# CPU_-_POWER_RAILS.net
KiCad netlist of a schematic drawn in Altium Designer
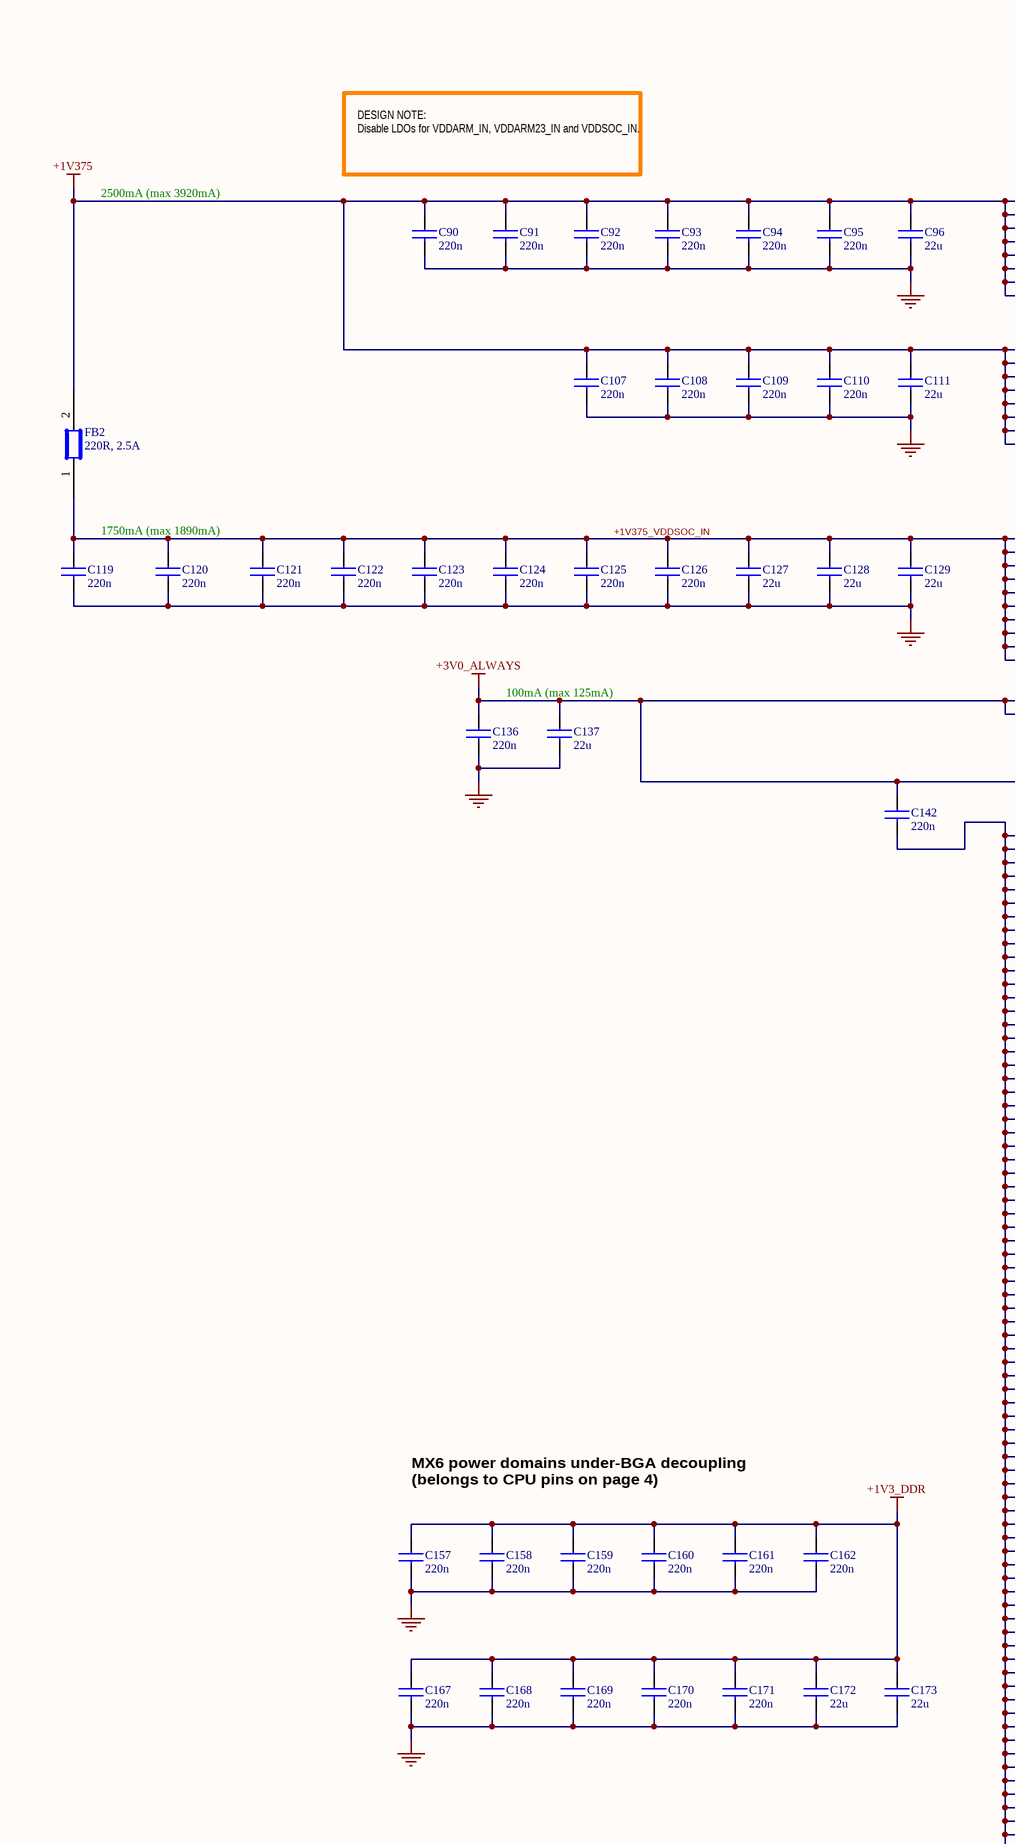
[diagram p0: CPU - POWER RAILS.SchDoc, left]
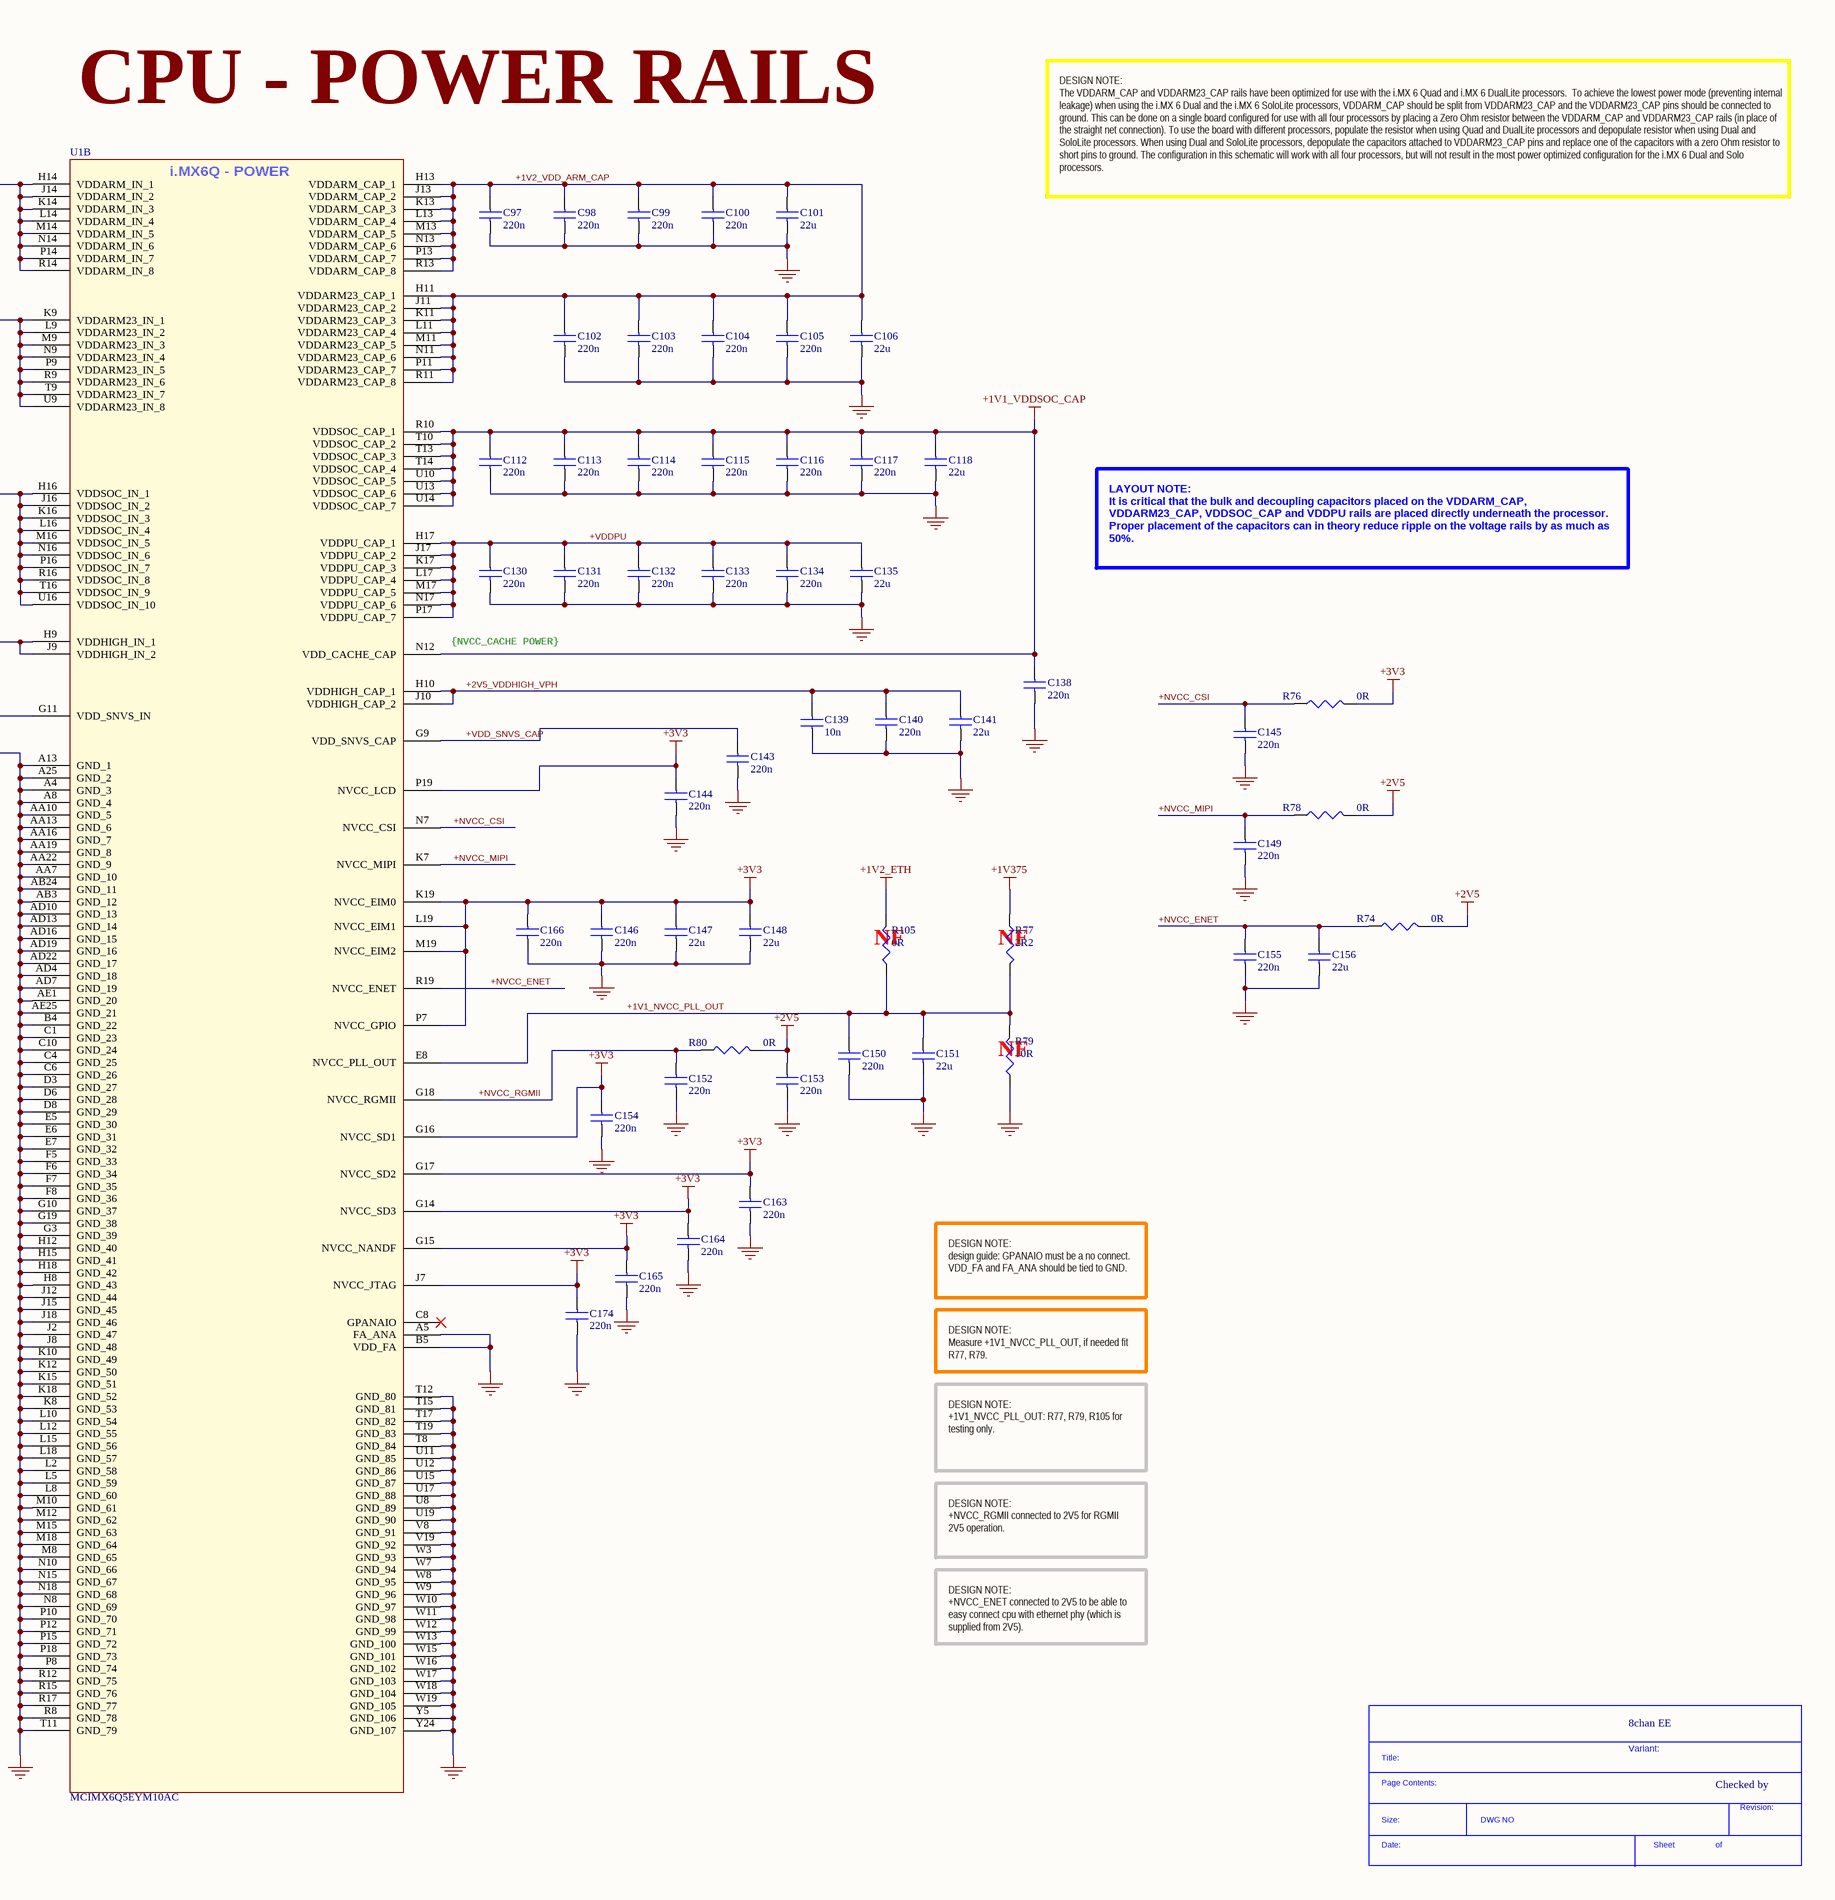
[diagram p1: CPU - POWER RAILS.SchDoc, right]

(export (version "E")
  (design (tool "Eeschema 10.0.6"))
  (components
    (comp (ref "*") (value "SDTitleBlock") (libsource (lib "*") (part "SDTitleBlock")))
    (comp (ref "C90")
      (value "220n")
      (footprint "C0402")
      (description "CAP CER .22UF 25V X5R 20% 0402")
      (fields
        (field (name "MANUFACTURER") "TDK Corporation")
        (field (name "MANUFACTURER PART NUMBER") "C1005X5R1E224M")
      )
      (libsource (lib "Integrated_Library_RF_FEB_2012") (part "C1005X5R1E224M"))
    )
    (comp (ref "C91")
      (value "220n")
      (footprint "C0402")
      (description "CAP CER .22UF 25V X5R 20% 0402")
      (fields
        (field (name "MANUFACTURER") "TDK Corporation")
        (field (name "MANUFACTURER PART NUMBER") "C1005X5R1E224M")
      )
      (libsource (lib "Integrated_Library_RF_FEB_2012") (part "C1005X5R1E224M"))
    )
    (comp (ref "C92")
      (value "220n")
      (footprint "C0402")
      (description "CAP CER .22UF 25V X5R 20% 0402")
      (fields
        (field (name "MANUFACTURER") "TDK Corporation")
        (field (name "MANUFACTURER PART NUMBER") "C1005X5R1E224M")
      )
      (libsource (lib "Integrated_Library_RF_FEB_2012") (part "C1005X5R1E224M"))
    )
    (comp (ref "C93")
      (value "220n")
      (footprint "C0402")
      (description "CAP CER .22UF 25V X5R 20% 0402")
      (fields
        (field (name "MANUFACTURER") "TDK Corporation")
        (field (name "MANUFACTURER PART NUMBER") "C1005X5R1E224M")
      )
      (libsource (lib "Integrated_Library_RF_FEB_2012") (part "C1005X5R1E224M"))
    )
    (comp (ref "C94")
      (value "220n")
      (footprint "C0402")
      (description "CAP CER .22UF 25V X5R 20% 0402")
      (fields
        (field (name "MANUFACTURER") "TDK Corporation")
        (field (name "MANUFACTURER PART NUMBER") "C1005X5R1E224M")
      )
      (libsource (lib "Integrated_Library_RF_FEB_2012") (part "C1005X5R1E224M"))
    )
    (comp (ref "C95")
      (value "220n")
      (footprint "C0402")
      (description "CAP CER .22UF 25V X5R 20% 0402")
      (fields
        (field (name "MANUFACTURER") "TDK Corporation")
        (field (name "MANUFACTURER PART NUMBER") "C1005X5R1E224M")
      )
      (libsource (lib "Integrated_Library_RF_FEB_2012") (part "C1005X5R1E224M"))
    )
    (comp (ref "C96")
      (value "22u")
      (footprint "C0603")
      (description "CAP CER 22UF 4V 20% X5R 0603")
      (fields
        (field (name "MANUFACTURER") "Murata Electronics North America")
        (field (name "MANUFACTURER PART NUMBER") "GRM188R60G226MEA0L")
        (field (name ".CHECKED PCB") "RF, used by MM")
        (field (name ".CHECKED SCH") "MM, checked by RF")
        (field (name ".CREATOR") "MM")
      )
      (libsource (lib "Schlib_RF") (part "GRM188R60G226MEA0L"))
    )
    (comp (ref "C97")
      (value "220n")
      (footprint "C0402")
      (description "CAP CER .22UF 25V X5R 20% 0402")
      (fields
        (field (name "MANUFACTURER") "TDK Corporation")
        (field (name "MANUFACTURER PART NUMBER") "C1005X5R1E224M")
      )
      (libsource (lib "Integrated_Library_RF_FEB_2012") (part "C1005X5R1E224M"))
    )
    (comp (ref "C98")
      (value "220n")
      (footprint "C0402")
      (description "CAP CER .22UF 25V X5R 20% 0402")
      (fields
        (field (name "MANUFACTURER") "TDK Corporation")
        (field (name "MANUFACTURER PART NUMBER") "C1005X5R1E224M")
      )
      (libsource (lib "Integrated_Library_RF_FEB_2012") (part "C1005X5R1E224M"))
    )
    (comp (ref "C99")
      (value "220n")
      (footprint "C0402")
      (description "CAP CER .22UF 25V X5R 20% 0402")
      (fields
        (field (name "MANUFACTURER") "TDK Corporation")
        (field (name "MANUFACTURER PART NUMBER") "C1005X5R1E224M")
      )
      (libsource (lib "Integrated_Library_RF_FEB_2012") (part "C1005X5R1E224M"))
    )
    (comp (ref "C100")
      (value "220n")
      (footprint "C0402")
      (description "CAP CER .22UF 25V X5R 20% 0402")
      (fields
        (field (name "MANUFACTURER") "TDK Corporation")
        (field (name "MANUFACTURER PART NUMBER") "C1005X5R1E224M")
      )
      (libsource (lib "Integrated_Library_RF_FEB_2012") (part "C1005X5R1E224M"))
    )
    (comp (ref "C101")
      (value "22u")
      (footprint "C0603")
      (description "CAP CER 22UF 4V 20% X5R 0603")
      (fields
        (field (name "MANUFACTURER") "Murata Electronics North America")
        (field (name "MANUFACTURER PART NUMBER") "GRM188R60G226MEA0L")
        (field (name ".CHECKED PCB") "RF, used by MM")
        (field (name ".CHECKED SCH") "MM, checked by RF")
        (field (name ".CREATOR") "MM")
      )
      (libsource (lib "Schlib_RF") (part "GRM188R60G226MEA0L"))
    )
    (comp (ref "C102")
      (value "220n")
      (footprint "C0402")
      (description "CAP CER .22UF 25V X5R 20% 0402")
      (fields
        (field (name "MANUFACTURER") "TDK Corporation")
        (field (name "MANUFACTURER PART NUMBER") "C1005X5R1E224M")
      )
      (libsource (lib "Integrated_Library_RF_FEB_2012") (part "C1005X5R1E224M"))
    )
    (comp (ref "C103")
      (value "220n")
      (footprint "C0402")
      (description "CAP CER .22UF 25V X5R 20% 0402")
      (fields
        (field (name "MANUFACTURER") "TDK Corporation")
        (field (name "MANUFACTURER PART NUMBER") "C1005X5R1E224M")
      )
      (libsource (lib "Integrated_Library_RF_FEB_2012") (part "C1005X5R1E224M"))
    )
    (comp (ref "C104")
      (value "220n")
      (footprint "C0402")
      (description "CAP CER .22UF 25V X5R 20% 0402")
      (fields
        (field (name "MANUFACTURER") "TDK Corporation")
        (field (name "MANUFACTURER PART NUMBER") "C1005X5R1E224M")
      )
      (libsource (lib "Integrated_Library_RF_FEB_2012") (part "C1005X5R1E224M"))
    )
    (comp (ref "C105")
      (value "220n")
      (footprint "C0402")
      (description "CAP CER .22UF 25V X5R 20% 0402")
      (fields
        (field (name "MANUFACTURER") "TDK Corporation")
        (field (name "MANUFACTURER PART NUMBER") "C1005X5R1E224M")
      )
      (libsource (lib "Integrated_Library_RF_FEB_2012") (part "C1005X5R1E224M"))
    )
    (comp (ref "C106")
      (value "22u")
      (footprint "C0603")
      (description "CAP CER 22UF 4V 20% X5R 0603")
      (fields
        (field (name "MANUFACTURER") "Murata Electronics North America")
        (field (name "MANUFACTURER PART NUMBER") "GRM188R60G226MEA0L")
        (field (name ".CHECKED PCB") "RF, used by MM")
        (field (name ".CHECKED SCH") "MM, checked by RF")
        (field (name ".CREATOR") "MM")
      )
      (libsource (lib "Schlib_RF") (part "GRM188R60G226MEA0L"))
    )
    (comp (ref "C107")
      (value "220n")
      (footprint "C0402")
      (description "CAP CER .22UF 25V X5R 20% 0402")
      (fields
        (field (name "MANUFACTURER") "TDK Corporation")
        (field (name "MANUFACTURER PART NUMBER") "C1005X5R1E224M")
      )
      (libsource (lib "Integrated_Library_RF_FEB_2012") (part "C1005X5R1E224M"))
    )
    (comp (ref "C108")
      (value "220n")
      (footprint "C0402")
      (description "CAP CER .22UF 25V X5R 20% 0402")
      (fields
        (field (name "MANUFACTURER") "TDK Corporation")
        (field (name "MANUFACTURER PART NUMBER") "C1005X5R1E224M")
      )
      (libsource (lib "Integrated_Library_RF_FEB_2012") (part "C1005X5R1E224M"))
    )
    (comp (ref "C109")
      (value "220n")
      (footprint "C0402")
      (description "CAP CER .22UF 25V X5R 20% 0402")
      (fields
        (field (name "MANUFACTURER") "TDK Corporation")
        (field (name "MANUFACTURER PART NUMBER") "C1005X5R1E224M")
      )
      (libsource (lib "Integrated_Library_RF_FEB_2012") (part "C1005X5R1E224M"))
    )
    (comp (ref "C110")
      (value "220n")
      (footprint "C0402")
      (description "CAP CER .22UF 25V X5R 20% 0402")
      (fields
        (field (name "MANUFACTURER") "TDK Corporation")
        (field (name "MANUFACTURER PART NUMBER") "C1005X5R1E224M")
      )
      (libsource (lib "Integrated_Library_RF_FEB_2012") (part "C1005X5R1E224M"))
    )
    (comp (ref "C111")
      (value "22u")
      (footprint "C0603")
      (description "CAP CER 22UF 4V 20% X5R 0603")
      (fields
        (field (name "MANUFACTURER") "Murata Electronics North America")
        (field (name "MANUFACTURER PART NUMBER") "GRM188R60G226MEA0L")
        (field (name ".CHECKED PCB") "RF, used by MM")
        (field (name ".CHECKED SCH") "MM, checked by RF")
        (field (name ".CREATOR") "MM")
      )
      (libsource (lib "Schlib_RF") (part "GRM188R60G226MEA0L"))
    )
    (comp (ref "C112")
      (value "220n")
      (footprint "C0402")
      (description "CAP CER .22UF 25V X5R 20% 0402")
      (fields
        (field (name "MANUFACTURER") "TDK Corporation")
        (field (name "MANUFACTURER PART NUMBER") "C1005X5R1E224M")
      )
      (libsource (lib "Integrated_Library_RF_FEB_2012") (part "C1005X5R1E224M"))
    )
    (comp (ref "C113")
      (value "220n")
      (footprint "C0402")
      (description "CAP CER .22UF 25V X5R 20% 0402")
      (fields
        (field (name "MANUFACTURER") "TDK Corporation")
        (field (name "MANUFACTURER PART NUMBER") "C1005X5R1E224M")
      )
      (libsource (lib "Integrated_Library_RF_FEB_2012") (part "C1005X5R1E224M"))
    )
    (comp (ref "C114")
      (value "220n")
      (footprint "C0402")
      (description "CAP CER .22UF 25V X5R 20% 0402")
      (fields
        (field (name "MANUFACTURER") "TDK Corporation")
        (field (name "MANUFACTURER PART NUMBER") "C1005X5R1E224M")
      )
      (libsource (lib "Integrated_Library_RF_FEB_2012") (part "C1005X5R1E224M"))
    )
    (comp (ref "C115")
      (value "220n")
      (footprint "C0402")
      (description "CAP CER .22UF 25V X5R 20% 0402")
      (fields
        (field (name "MANUFACTURER") "TDK Corporation")
        (field (name "MANUFACTURER PART NUMBER") "C1005X5R1E224M")
      )
      (libsource (lib "Integrated_Library_RF_FEB_2012") (part "C1005X5R1E224M"))
    )
    (comp (ref "C116")
      (value "220n")
      (footprint "C0402")
      (description "CAP CER .22UF 25V X5R 20% 0402")
      (fields
        (field (name "MANUFACTURER") "TDK Corporation")
        (field (name "MANUFACTURER PART NUMBER") "C1005X5R1E224M")
      )
      (libsource (lib "Integrated_Library_RF_FEB_2012") (part "C1005X5R1E224M"))
    )
    (comp (ref "C117")
      (value "220n")
      (footprint "C0402")
      (description "CAP CER .22UF 25V X5R 20% 0402")
      (fields
        (field (name "MANUFACTURER") "TDK Corporation")
        (field (name "MANUFACTURER PART NUMBER") "C1005X5R1E224M")
      )
      (libsource (lib "Integrated_Library_RF_FEB_2012") (part "C1005X5R1E224M"))
    )
    (comp (ref "C118")
      (value "22u")
      (footprint "C0603")
      (description "CAP CER 22UF 4V 20% X5R 0603")
      (fields
        (field (name "MANUFACTURER") "Murata Electronics North America")
        (field (name "MANUFACTURER PART NUMBER") "GRM188R60G226MEA0L")
        (field (name ".CHECKED PCB") "RF, used by MM")
        (field (name ".CHECKED SCH") "MM, checked by RF")
        (field (name ".CREATOR") "MM")
      )
      (libsource (lib "Schlib_RF") (part "GRM188R60G226MEA0L"))
    )
    (comp (ref "C119")
      (value "220n")
      (footprint "C0402")
      (description "CAP CER .22UF 25V X5R 20% 0402")
      (fields
        (field (name "MANUFACTURER") "TDK Corporation")
        (field (name "MANUFACTURER PART NUMBER") "C1005X5R1E224M")
      )
      (libsource (lib "Integrated_Library_RF_FEB_2012") (part "C1005X5R1E224M"))
    )
    (comp (ref "C120")
      (value "220n")
      (footprint "C0402")
      (description "CAP CER .22UF 25V X5R 20% 0402")
      (fields
        (field (name "MANUFACTURER") "TDK Corporation")
        (field (name "MANUFACTURER PART NUMBER") "C1005X5R1E224M")
      )
      (libsource (lib "Integrated_Library_RF_FEB_2012") (part "C1005X5R1E224M"))
    )
    (comp (ref "C121")
      (value "220n")
      (footprint "C0402")
      (description "CAP CER .22UF 25V X5R 20% 0402")
      (fields
        (field (name "MANUFACTURER") "TDK Corporation")
        (field (name "MANUFACTURER PART NUMBER") "C1005X5R1E224M")
      )
      (libsource (lib "Integrated_Library_RF_FEB_2012") (part "C1005X5R1E224M"))
    )
    (comp (ref "C122")
      (value "220n")
      (footprint "C0402")
      (description "CAP CER .22UF 25V X5R 20% 0402")
      (fields
        (field (name "MANUFACTURER") "TDK Corporation")
        (field (name "MANUFACTURER PART NUMBER") "C1005X5R1E224M")
      )
      (libsource (lib "Integrated_Library_RF_FEB_2012") (part "C1005X5R1E224M"))
    )
    (comp (ref "C123")
      (value "220n")
      (footprint "C0402")
      (description "CAP CER .22UF 25V X5R 20% 0402")
      (fields
        (field (name "MANUFACTURER") "TDK Corporation")
        (field (name "MANUFACTURER PART NUMBER") "C1005X5R1E224M")
      )
      (libsource (lib "Integrated_Library_RF_FEB_2012") (part "C1005X5R1E224M"))
    )
    (comp (ref "C124")
      (value "220n")
      (footprint "C0402")
      (description "CAP CER .22UF 25V X5R 20% 0402")
      (fields
        (field (name "MANUFACTURER") "TDK Corporation")
        (field (name "MANUFACTURER PART NUMBER") "C1005X5R1E224M")
      )
      (libsource (lib "Integrated_Library_RF_FEB_2012") (part "C1005X5R1E224M"))
    )
    (comp (ref "C125")
      (value "220n")
      (footprint "C0402")
      (description "CAP CER .22UF 25V X5R 20% 0402")
      (fields
        (field (name "MANUFACTURER") "TDK Corporation")
        (field (name "MANUFACTURER PART NUMBER") "C1005X5R1E224M")
      )
      (libsource (lib "Integrated_Library_RF_FEB_2012") (part "C1005X5R1E224M"))
    )
    (comp (ref "C126")
      (value "220n")
      (footprint "C0402")
      (description "CAP CER .22UF 25V X5R 20% 0402")
      (fields
        (field (name "MANUFACTURER") "TDK Corporation")
        (field (name "MANUFACTURER PART NUMBER") "C1005X5R1E224M")
      )
      (libsource (lib "Integrated_Library_RF_FEB_2012") (part "C1005X5R1E224M"))
    )
    (comp (ref "C127")
      (value "22u")
      (footprint "C0603")
      (description "CAP CER 22UF 4V 20% X5R 0603")
      (fields
        (field (name "MANUFACTURER") "Murata Electronics North America")
        (field (name "MANUFACTURER PART NUMBER") "GRM188R60G226MEA0L")
        (field (name ".CHECKED PCB") "RF, used by MM")
        (field (name ".CHECKED SCH") "MM, checked by RF")
        (field (name ".CREATOR") "MM")
      )
      (libsource (lib "Schlib_RF") (part "GRM188R60G226MEA0L"))
    )
    (comp (ref "C128")
      (value "22u")
      (footprint "C0603")
      (description "CAP CER 22UF 4V 20% X5R 0603")
      (fields
        (field (name "MANUFACTURER") "Murata Electronics North America")
        (field (name "MANUFACTURER PART NUMBER") "GRM188R60G226MEA0L")
        (field (name ".CHECKED PCB") "RF, used by MM")
        (field (name ".CHECKED SCH") "MM, checked by RF")
        (field (name ".CREATOR") "MM")
      )
      (libsource (lib "Schlib_RF") (part "GRM188R60G226MEA0L"))
    )
    (comp (ref "C129")
      (value "22u")
      (footprint "C0603")
      (description "CAP CER 22UF 4V 20% X5R 0603")
      (fields
        (field (name "MANUFACTURER") "Murata Electronics North America")
        (field (name "MANUFACTURER PART NUMBER") "GRM188R60G226MEA0L")
        (field (name ".CHECKED PCB") "RF, used by MM")
        (field (name ".CHECKED SCH") "MM, checked by RF")
        (field (name ".CREATOR") "MM")
      )
      (libsource (lib "Schlib_RF") (part "GRM188R60G226MEA0L"))
    )
    (comp (ref "C130")
      (value "220n")
      (footprint "C0402")
      (description "CAP CER .22UF 25V X5R 20% 0402")
      (fields
        (field (name "MANUFACTURER") "TDK Corporation")
        (field (name "MANUFACTURER PART NUMBER") "C1005X5R1E224M")
      )
      (libsource (lib "Integrated_Library_RF_FEB_2012") (part "C1005X5R1E224M"))
    )
    (comp (ref "C131")
      (value "220n")
      (footprint "C0402")
      (description "CAP CER .22UF 25V X5R 20% 0402")
      (fields
        (field (name "MANUFACTURER") "TDK Corporation")
        (field (name "MANUFACTURER PART NUMBER") "C1005X5R1E224M")
      )
      (libsource (lib "Integrated_Library_RF_FEB_2012") (part "C1005X5R1E224M"))
    )
    (comp (ref "C132")
      (value "220n")
      (footprint "C0402")
      (description "CAP CER .22UF 25V X5R 20% 0402")
      (fields
        (field (name "MANUFACTURER") "TDK Corporation")
        (field (name "MANUFACTURER PART NUMBER") "C1005X5R1E224M")
      )
      (libsource (lib "Integrated_Library_RF_FEB_2012") (part "C1005X5R1E224M"))
    )
    (comp (ref "C133")
      (value "220n")
      (footprint "C0402")
      (description "CAP CER .22UF 25V X5R 20% 0402")
      (fields
        (field (name "MANUFACTURER") "TDK Corporation")
        (field (name "MANUFACTURER PART NUMBER") "C1005X5R1E224M")
      )
      (libsource (lib "Integrated_Library_RF_FEB_2012") (part "C1005X5R1E224M"))
    )
    (comp (ref "C134")
      (value "220n")
      (footprint "C0402")
      (description "CAP CER .22UF 25V X5R 20% 0402")
      (fields
        (field (name "MANUFACTURER") "TDK Corporation")
        (field (name "MANUFACTURER PART NUMBER") "C1005X5R1E224M")
      )
      (libsource (lib "Integrated_Library_RF_FEB_2012") (part "C1005X5R1E224M"))
    )
    (comp (ref "C135")
      (value "22u")
      (footprint "C0603")
      (description "CAP CER 22UF 4V 20% X5R 0603")
      (fields
        (field (name "MANUFACTURER") "Murata Electronics North America")
        (field (name "MANUFACTURER PART NUMBER") "GRM188R60G226MEA0L")
        (field (name ".CHECKED PCB") "RF, used by MM")
        (field (name ".CHECKED SCH") "MM, checked by RF")
        (field (name ".CREATOR") "MM")
      )
      (libsource (lib "Schlib_RF") (part "GRM188R60G226MEA0L"))
    )
    (comp (ref "C136")
      (value "220n")
      (footprint "C0402")
      (description "CAP CER .22UF 25V X5R 20% 0402")
      (fields
        (field (name "MANUFACTURER") "TDK Corporation")
        (field (name "MANUFACTURER PART NUMBER") "C1005X5R1E224M")
      )
      (libsource (lib "Integrated_Library_RF_FEB_2012") (part "C1005X5R1E224M"))
    )
    (comp (ref "C137")
      (value "22u")
      (footprint "C0805")
      (description "CAP CER 22UF 16V 10% X5R 0805")
      (fields
        (field (name "MANUFACTURER") "TDK Corporation")
        (field (name "MANUFACTURER PART NUMBER") "C2012X5R1C226K")
        (field (name ".CHECKED PCB") "RF")
        (field (name ".CHECKED SCH") "RF")
      )
      (libsource (lib "Integrated_Library_RF_FEB_2012") (part "C2012X5R1C226K"))
    )
    (comp (ref "C138")
      (value "220n")
      (footprint "C0402")
      (description "CAP CER .22UF 25V X5R 20% 0402")
      (fields
        (field (name "MANUFACTURER") "TDK Corporation")
        (field (name "MANUFACTURER PART NUMBER") "C1005X5R1E224M")
      )
      (libsource (lib "Integrated_Library_RF_FEB_2012") (part "C1005X5R1E224M"))
    )
    (comp (ref "C139")
      (value "10n")
      (footprint "C0402")
      (description "CAP CER 10000PF 50V 10% X7R 0402")
      (fields
        (field (name "MANUFACTURER") "TDK Corporation")
        (field (name "MANUFACTURER PART NUMBER") "C1005X7R1H103K")
        (field (name ".CHECKED PCB") "RF")
        (field (name ".CHECKED SCH") "RF")
      )
      (libsource (lib "Integrated_Library_RF_FEB_2012") (part "C1005X7R1H103K"))
    )
    (comp (ref "C140")
      (value "220n")
      (footprint "C0402")
      (description "CAP CER .22UF 25V X5R 20% 0402")
      (fields
        (field (name "MANUFACTURER") "TDK Corporation")
        (field (name "MANUFACTURER PART NUMBER") "C1005X5R1E224M")
      )
      (libsource (lib "Integrated_Library_RF_FEB_2012") (part "C1005X5R1E224M"))
    )
    (comp (ref "C141")
      (value "22u")
      (footprint "C0805")
      (description "CAP CER 22UF 16V 10% X5R 0805")
      (fields
        (field (name "MANUFACTURER") "TDK Corporation")
        (field (name "MANUFACTURER PART NUMBER") "C2012X5R1C226K")
        (field (name ".CHECKED PCB") "RF")
        (field (name ".CHECKED SCH") "RF")
      )
      (libsource (lib "Integrated_Library_RF_FEB_2012") (part "C2012X5R1C226K"))
    )
    (comp (ref "C142")
      (value "220n")
      (footprint "C0402")
      (description "CAP CER .22UF 25V X5R 20% 0402")
      (fields
        (field (name "MANUFACTURER") "TDK Corporation")
        (field (name "MANUFACTURER PART NUMBER") "C1005X5R1E224M")
      )
      (libsource (lib "Integrated_Library_RF_FEB_2012") (part "C1005X5R1E224M"))
    )
    (comp (ref "C143")
      (value "220n")
      (footprint "C0402")
      (description "CAP CER .22UF 25V X5R 20% 0402")
      (fields
        (field (name "MANUFACTURER") "TDK Corporation")
        (field (name "MANUFACTURER PART NUMBER") "C1005X5R1E224M")
      )
      (libsource (lib "Integrated_Library_RF_FEB_2012") (part "C1005X5R1E224M"))
    )
    (comp (ref "C144")
      (value "220n")
      (footprint "C0402")
      (description "CAP CER .22UF 25V X5R 20% 0402")
      (fields
        (field (name "MANUFACTURER") "TDK Corporation")
        (field (name "MANUFACTURER PART NUMBER") "C1005X5R1E224M")
      )
      (libsource (lib "Integrated_Library_RF_FEB_2012") (part "C1005X5R1E224M"))
    )
    (comp (ref "C145")
      (value "220n")
      (footprint "C0402")
      (description "CAP CER .22UF 25V X5R 20% 0402")
      (fields
        (field (name "MANUFACTURER") "TDK Corporation")
        (field (name "MANUFACTURER PART NUMBER") "C1005X5R1E224M")
      )
      (libsource (lib "Integrated_Library_RF_FEB_2012") (part "C1005X5R1E224M"))
    )
    (comp (ref "C146")
      (value "220n")
      (footprint "C0402")
      (description "CAP CER .22UF 25V X5R 20% 0402")
      (fields
        (field (name "MANUFACTURER") "TDK Corporation")
        (field (name "MANUFACTURER PART NUMBER") "C1005X5R1E224M")
      )
      (libsource (lib "Integrated_Library_RF_FEB_2012") (part "C1005X5R1E224M"))
    )
    (comp (ref "C147")
      (value "22u")
      (footprint "C0805")
      (description "CAP CER 22UF 16V 10% X5R 0805")
      (fields
        (field (name "MANUFACTURER") "TDK Corporation")
        (field (name "MANUFACTURER PART NUMBER") "C2012X5R1C226K")
        (field (name ".CHECKED PCB") "RF")
        (field (name ".CHECKED SCH") "RF")
      )
      (libsource (lib "Integrated_Library_RF_FEB_2012") (part "C2012X5R1C226K"))
    )
    (comp (ref "C148")
      (value "22u")
      (footprint "C0805")
      (description "CAP CER 22UF 16V 10% X5R 0805")
      (fields
        (field (name "MANUFACTURER") "TDK Corporation")
        (field (name "MANUFACTURER PART NUMBER") "C2012X5R1C226K")
        (field (name ".CHECKED PCB") "RF")
        (field (name ".CHECKED SCH") "RF")
      )
      (libsource (lib "Integrated_Library_RF_FEB_2012") (part "C2012X5R1C226K"))
    )
    (comp (ref "C149")
      (value "220n")
      (footprint "C0402")
      (description "CAP CER .22UF 25V X5R 20% 0402")
      (fields
        (field (name "MANUFACTURER") "TDK Corporation")
        (field (name "MANUFACTURER PART NUMBER") "C1005X5R1E224M")
      )
      (libsource (lib "Integrated_Library_RF_FEB_2012") (part "C1005X5R1E224M"))
    )
    (comp (ref "C150")
      (value "220n")
      (footprint "C0402")
      (description "CAP CER .22UF 25V X5R 20% 0402")
      (fields
        (field (name "MANUFACTURER") "TDK Corporation")
        (field (name "MANUFACTURER PART NUMBER") "C1005X5R1E224M")
      )
      (libsource (lib "Integrated_Library_RF_FEB_2012") (part "C1005X5R1E224M"))
    )
    (comp (ref "C151")
      (value "22u")
      (footprint "C0603")
      (description "CAP CER 22UF 4V 20% X5R 0603")
      (fields
        (field (name "MANUFACTURER") "Murata Electronics North America")
        (field (name "MANUFACTURER PART NUMBER") "GRM188R60G226MEA0L")
        (field (name ".CHECKED PCB") "RF, used by MM")
        (field (name ".CHECKED SCH") "MM, checked by RF")
        (field (name ".CREATOR") "MM")
      )
      (libsource (lib "Schlib_RF") (part "GRM188R60G226MEA0L"))
    )
    (comp (ref "C152")
      (value "220n")
      (footprint "C0402")
      (description "CAP CER .22UF 25V X5R 20% 0402")
      (fields
        (field (name "MANUFACTURER") "TDK Corporation")
        (field (name "MANUFACTURER PART NUMBER") "C1005X5R1E224M")
      )
      (libsource (lib "Integrated_Library_RF_FEB_2012") (part "C1005X5R1E224M"))
    )
    (comp (ref "C153")
      (value "220n")
      (footprint "C0402")
      (description "CAP CER .22UF 25V X5R 20% 0402")
      (fields
        (field (name "MANUFACTURER") "TDK Corporation")
        (field (name "MANUFACTURER PART NUMBER") "C1005X5R1E224M")
      )
      (libsource (lib "Integrated_Library_RF_FEB_2012") (part "C1005X5R1E224M"))
    )
    (comp (ref "C154")
      (value "220n")
      (footprint "C0402")
      (description "CAP CER .22UF 25V X5R 20% 0402")
      (fields
        (field (name "MANUFACTURER") "TDK Corporation")
        (field (name "MANUFACTURER PART NUMBER") "C1005X5R1E224M")
      )
      (libsource (lib "Integrated_Library_RF_FEB_2012") (part "C1005X5R1E224M"))
    )
    (comp (ref "C155")
      (value "220n")
      (footprint "C0402")
      (description "CAP CER .22UF 25V X5R 20% 0402")
      (fields
        (field (name "MANUFACTURER") "TDK Corporation")
        (field (name "MANUFACTURER PART NUMBER") "C1005X5R1E224M")
      )
      (libsource (lib "Integrated_Library_RF_FEB_2012") (part "C1005X5R1E224M"))
    )
    (comp (ref "C156")
      (value "22u")
      (footprint "C0805")
      (description "CAP CER 22UF 16V 10% X5R 0805")
      (fields
        (field (name "MANUFACTURER") "TDK Corporation")
        (field (name "MANUFACTURER PART NUMBER") "C2012X5R1C226K")
        (field (name ".CHECKED PCB") "RF")
        (field (name ".CHECKED SCH") "RF")
      )
      (libsource (lib "Integrated_Library_RF_FEB_2012") (part "C2012X5R1C226K"))
    )
    (comp (ref "C157")
      (value "220n")
      (footprint "C0402")
      (description "CAP CER .22UF 25V X5R 20% 0402")
      (fields
        (field (name "MANUFACTURER") "TDK Corporation")
        (field (name "MANUFACTURER PART NUMBER") "C1005X5R1E224M")
      )
      (libsource (lib "Integrated_Library_RF_FEB_2012") (part "C1005X5R1E224M"))
    )
    (comp (ref "C158")
      (value "220n")
      (footprint "C0402")
      (description "CAP CER .22UF 25V X5R 20% 0402")
      (fields
        (field (name "MANUFACTURER") "TDK Corporation")
        (field (name "MANUFACTURER PART NUMBER") "C1005X5R1E224M")
      )
      (libsource (lib "Integrated_Library_RF_FEB_2012") (part "C1005X5R1E224M"))
    )
    (comp (ref "C159")
      (value "220n")
      (footprint "C0402")
      (description "CAP CER .22UF 25V X5R 20% 0402")
      (fields
        (field (name "MANUFACTURER") "TDK Corporation")
        (field (name "MANUFACTURER PART NUMBER") "C1005X5R1E224M")
      )
      (libsource (lib "Integrated_Library_RF_FEB_2012") (part "C1005X5R1E224M"))
    )
    (comp (ref "C160")
      (value "220n")
      (footprint "C0402")
      (description "CAP CER .22UF 25V X5R 20% 0402")
      (fields
        (field (name "MANUFACTURER") "TDK Corporation")
        (field (name "MANUFACTURER PART NUMBER") "C1005X5R1E224M")
      )
      (libsource (lib "Integrated_Library_RF_FEB_2012") (part "C1005X5R1E224M"))
    )
    (comp (ref "C161")
      (value "220n")
      (footprint "C0402")
      (description "CAP CER .22UF 25V X5R 20% 0402")
      (fields
        (field (name "MANUFACTURER") "TDK Corporation")
        (field (name "MANUFACTURER PART NUMBER") "C1005X5R1E224M")
      )
      (libsource (lib "Integrated_Library_RF_FEB_2012") (part "C1005X5R1E224M"))
    )
    (comp (ref "C162")
      (value "220n")
      (footprint "C0402")
      (description "CAP CER .22UF 25V X5R 20% 0402")
      (fields
        (field (name "MANUFACTURER") "TDK Corporation")
        (field (name "MANUFACTURER PART NUMBER") "C1005X5R1E224M")
      )
      (libsource (lib "Integrated_Library_RF_FEB_2012") (part "C1005X5R1E224M"))
    )
    (comp (ref "C163")
      (value "220n")
      (footprint "C0402")
      (description "CAP CER .22UF 25V X5R 20% 0402")
      (fields
        (field (name "MANUFACTURER") "TDK Corporation")
        (field (name "MANUFACTURER PART NUMBER") "C1005X5R1E224M")
      )
      (libsource (lib "Integrated_Library_RF_FEB_2012") (part "C1005X5R1E224M"))
    )
    (comp (ref "C164")
      (value "220n")
      (footprint "C0402")
      (description "CAP CER .22UF 25V X5R 20% 0402")
      (fields
        (field (name "MANUFACTURER") "TDK Corporation")
        (field (name "MANUFACTURER PART NUMBER") "C1005X5R1E224M")
      )
      (libsource (lib "Integrated_Library_RF_FEB_2012") (part "C1005X5R1E224M"))
    )
    (comp (ref "C165")
      (value "220n")
      (footprint "C0402")
      (description "CAP CER .22UF 25V X5R 20% 0402")
      (fields
        (field (name "MANUFACTURER") "TDK Corporation")
        (field (name "MANUFACTURER PART NUMBER") "C1005X5R1E224M")
      )
      (libsource (lib "Integrated_Library_RF_FEB_2012") (part "C1005X5R1E224M"))
    )
    (comp (ref "C166")
      (value "220n")
      (footprint "C0402")
      (description "CAP CER .22UF 25V X5R 20% 0402")
      (fields
        (field (name "MANUFACTURER") "TDK Corporation")
        (field (name "MANUFACTURER PART NUMBER") "C1005X5R1E224M")
      )
      (libsource (lib "Integrated_Library_RF_FEB_2012") (part "C1005X5R1E224M"))
    )
    (comp (ref "C167")
      (value "220n")
      (footprint "C0402")
      (description "CAP CER .22UF 25V X5R 20% 0402")
      (fields
        (field (name "MANUFACTURER") "TDK Corporation")
        (field (name "MANUFACTURER PART NUMBER") "C1005X5R1E224M")
      )
      (libsource (lib "Integrated_Library_RF_FEB_2012") (part "C1005X5R1E224M"))
    )
    (comp (ref "C168")
      (value "220n")
      (footprint "C0402")
      (description "CAP CER .22UF 25V X5R 20% 0402")
      (fields
        (field (name "MANUFACTURER") "TDK Corporation")
        (field (name "MANUFACTURER PART NUMBER") "C1005X5R1E224M")
      )
      (libsource (lib "Integrated_Library_RF_FEB_2012") (part "C1005X5R1E224M"))
    )
    (comp (ref "C169")
      (value "220n")
      (footprint "C0402")
      (description "CAP CER .22UF 25V X5R 20% 0402")
      (fields
        (field (name "MANUFACTURER") "TDK Corporation")
        (field (name "MANUFACTURER PART NUMBER") "C1005X5R1E224M")
      )
      (libsource (lib "Integrated_Library_RF_FEB_2012") (part "C1005X5R1E224M"))
    )
    (comp (ref "C170")
      (value "220n")
      (footprint "C0402")
      (description "CAP CER .22UF 25V X5R 20% 0402")
      (fields
        (field (name "MANUFACTURER") "TDK Corporation")
        (field (name "MANUFACTURER PART NUMBER") "C1005X5R1E224M")
      )
      (libsource (lib "Integrated_Library_RF_FEB_2012") (part "C1005X5R1E224M"))
    )
    (comp (ref "C171")
      (value "220n")
      (footprint "C0402")
      (description "CAP CER .22UF 25V X5R 20% 0402")
      (fields
        (field (name "MANUFACTURER") "TDK Corporation")
        (field (name "MANUFACTURER PART NUMBER") "C1005X5R1E224M")
      )
      (libsource (lib "Integrated_Library_RF_FEB_2012") (part "C1005X5R1E224M"))
    )
    (comp (ref "C172")
      (value "22u")
      (footprint "C0603")
      (description "CAP CER 22UF 4V 20% X5R 0603")
      (fields
        (field (name "MANUFACTURER") "Murata Electronics North America")
        (field (name "MANUFACTURER PART NUMBER") "GRM188R60G226MEA0L")
        (field (name ".CHECKED PCB") "RF, used by MM")
        (field (name ".CHECKED SCH") "MM, checked by RF")
        (field (name ".CREATOR") "MM")
      )
      (libsource (lib "Schlib_RF") (part "GRM188R60G226MEA0L"))
    )
    (comp (ref "C173")
      (value "22u")
      (footprint "C0603")
      (description "CAP CER 22UF 4V 20% X5R 0603")
      (fields
        (field (name "MANUFACTURER") "Murata Electronics North America")
        (field (name "MANUFACTURER PART NUMBER") "GRM188R60G226MEA0L")
        (field (name ".CHECKED PCB") "RF, used by MM")
        (field (name ".CHECKED SCH") "MM, checked by RF")
        (field (name ".CREATOR") "MM")
      )
      (libsource (lib "Schlib_RF") (part "GRM188R60G226MEA0L"))
    )
    (comp (ref "C174")
      (value "220n")
      (footprint "C0402")
      (description "CAP CER .22UF 25V X5R 20% 0402")
      (fields
        (field (name "MANUFACTURER") "TDK Corporation")
        (field (name "MANUFACTURER PART NUMBER") "C1005X5R1E224M")
      )
      (libsource (lib "Integrated_Library_RF_FEB_2012") (part "C1005X5R1E224M"))
    )
    (comp (ref "FB2")
      (value "220R, 2.5A")
      (footprint "C0603")
      (description "FERRITE CHIP 220 OHM 2500MA 0603")
      (fields
        (field (name "MANUFACTURER") "Murata Electronics North America")
        (field (name "MANUFACTURER PART NUMBER") "BLM18SG221TN1D")
        (field (name ".CHECKED PCB") "RF")
        (field (name ".CHECKED SCH") "RF")
      )
      (libsource (lib "Integrated_Library_RF_FEB_2012") (part "BLM18SG221TN1D"))
    )
    (comp (ref "R74")
      (value "0R")
      (footprint "R0402")
      (description "RES 0.0 OHM 1/16W 0402 SMD")
      (fields
        (field (name "MANUFACTURER") "Yageo")
        (field (name "MANUFACTURER PART NUMBER") "RC0402JR-070RL")
      )
      (libsource (lib "Integrated_Library_RF_FEB_2012") (part "RC0402JR-070RL"))
    )
    (comp (ref "R76")
      (value "0R")
      (footprint "R0402")
      (description "RES 0.0 OHM 1/16W 0402 SMD")
      (fields
        (field (name "MANUFACTURER") "Yageo")
        (field (name "MANUFACTURER PART NUMBER") "RC0402JR-070RL")
      )
      (libsource (lib "Integrated_Library_RF_FEB_2012") (part "RC0402JR-070RL"))
    )
    (comp (ref "R77")
      (value "2R2")
      (footprint "R0402")
      (description "RES 2.20 OHM 1/16W 1% 0402 SMD")
      (fields
        (field (name "MANUFACTURER") "Vishay Dale")
        (field (name "MANUFACTURER PART NUMBER") "CRCW04022R20FKED")
        (field (name ".CHECKED PCB") "RF")
        (field (name ".CHECKED SCH") "RF")
      )
      (libsource (lib "Integrated_Library_RF_FEB_2012") (part "CRCW04022R20FKED"))
    )
    (comp (ref "R78")
      (value "0R")
      (footprint "R0402")
      (description "RES 0.0 OHM 1/16W 0402 SMD")
      (fields
        (field (name "MANUFACTURER") "Yageo")
        (field (name "MANUFACTURER PART NUMBER") "RC0402JR-070RL")
      )
      (libsource (lib "Integrated_Library_RF_FEB_2012") (part "RC0402JR-070RL"))
    )
    (comp (ref "R79")
      (value "10R")
      (footprint "R0402")
      (description "RES 10.0 OHM 1/16W 1% 0402 SMD")
      (fields
        (field (name "MANUFACTURER") "Yageo")
        (field (name "MANUFACTURER PART NUMBER") "RC0402FR-0710RL")
      )
      (libsource (lib "Integrated_Library_RF_FEB_2012") (part "RC0402FR-0710RL"))
    )
    (comp (ref "R80")
      (value "0R")
      (footprint "R0402")
      (description "RES 0.0 OHM 1/16W 0402 SMD")
      (fields
        (field (name "MANUFACTURER") "Yageo")
        (field (name "MANUFACTURER PART NUMBER") "RC0402JR-070RL")
      )
      (libsource (lib "Integrated_Library_RF_FEB_2012") (part "RC0402JR-070RL"))
    )
    (comp (ref "R105")
      (value "0R")
      (footprint "R0402")
      (description "RES 0.0 OHM 1/16W 0402 SMD")
      (fields
        (field (name "MANUFACTURER") "Yageo")
        (field (name "MANUFACTURER PART NUMBER") "RC0402JR-070RL")
      )
      (libsource (lib "Integrated_Library_RF_FEB_2012") (part "RC0402JR-070RL"))
    )
    (comp (ref "U1")
      (value "MCIMX6Q5EYM10AC")
      (footprint "PBGA624")
      (description "IC MCU 32BIT ARM QUAD 624FCBGA")
      (fields
        (field (name "MANUFACTURER") "Freescale Semiconductor")
        (field (name ".CREATOR") "MM")
        (field (name ".CHECKED PCB") "MM, checked by RF")
        (field (name ".CHECKED SCH") "MM")
      )
      (libsource (lib "Schlib_RF") (part "MCIMX6Q5EYM10AC"))
    )
  )
  (nets
    (net (code "1") (name "+1V1_VDDSOC_CAP") (class "Default")
      (node (ref "C112") (pin "1") (pinfunction "1_1") (pintype "passive"))
      (node (ref "C113") (pin "1") (pinfunction "1_1") (pintype "passive"))
      (node (ref "C114") (pin "1") (pinfunction "1_1") (pintype "passive"))
      (node (ref "C115") (pin "1") (pinfunction "1_1") (pintype "passive"))
      (node (ref "C116") (pin "1") (pinfunction "1_1") (pintype "passive"))
      (node (ref "C117") (pin "1") (pinfunction "1_1") (pintype "passive"))
      (node (ref "C118") (pin "1") (pinfunction "1_1") (pintype "passive"))
      (node (ref "C138") (pin "1") (pinfunction "1_1") (pintype "passive"))
      (node (ref "U1") (pin "N12") (pinfunction "VDD_CACHE_CAP_N12") (pintype "power_in"))
      (node (ref "U1") (pin "R10") (pinfunction "VDDSOC_CAP_1_R10") (pintype "power_in"))
      (node (ref "U1") (pin "T10") (pinfunction "VDDSOC_CAP_2_T10") (pintype "power_in"))
      (node (ref "U1") (pin "T13") (pinfunction "VDDSOC_CAP_3_T13") (pintype "power_in"))
      (node (ref "U1") (pin "T14") (pinfunction "VDDSOC_CAP_4_T14") (pintype "power_in"))
      (node (ref "U1") (pin "U10") (pinfunction "VDDSOC_CAP_5_U10") (pintype "power_in"))
      (node (ref "U1") (pin "U13") (pinfunction "VDDSOC_CAP_6_U13") (pintype "power_in"))
      (node (ref "U1") (pin "U14") (pinfunction "VDDSOC_CAP_7_U14") (pintype "power_in"))
    )
    (net (code "2") (name "+1V2_ETH") (class "Default")
      (node (ref "R105") (pin "2") (pinfunction "2_2") (pintype "passive"))
    )
    (net (code "3") (name "+1V3_DDR") (class "Default")
      (node (ref "C157") (pin "1") (pinfunction "1_1") (pintype "passive"))
      (node (ref "C158") (pin "1") (pinfunction "1_1") (pintype "passive"))
      (node (ref "C159") (pin "1") (pinfunction "1_1") (pintype "passive"))
      (node (ref "C160") (pin "1") (pinfunction "1_1") (pintype "passive"))
      (node (ref "C161") (pin "1") (pinfunction "1_1") (pintype "passive"))
      (node (ref "C162") (pin "1") (pinfunction "1_1") (pintype "passive"))
      (node (ref "C167") (pin "1") (pinfunction "1_1") (pintype "passive"))
      (node (ref "C168") (pin "1") (pinfunction "1_1") (pintype "passive"))
      (node (ref "C169") (pin "1") (pinfunction "1_1") (pintype "passive"))
      (node (ref "C170") (pin "1") (pinfunction "1_1") (pintype "passive"))
      (node (ref "C171") (pin "1") (pinfunction "1_1") (pintype "passive"))
      (node (ref "C172") (pin "1") (pinfunction "1_1") (pintype "passive"))
      (node (ref "C173") (pin "1") (pinfunction "1_1") (pintype "passive"))
    )
    (net (code "4") (name "+1V375") (class "Default")
      (node (ref "C107") (pin "1") (pinfunction "1_1") (pintype "passive"))
      (node (ref "C108") (pin "1") (pinfunction "1_1") (pintype "passive"))
      (node (ref "C109") (pin "1") (pinfunction "1_1") (pintype "passive"))
      (node (ref "C110") (pin "1") (pinfunction "1_1") (pintype "passive"))
      (node (ref "C111") (pin "1") (pinfunction "1_1") (pintype "passive"))
      (node (ref "C90") (pin "1") (pinfunction "1_1") (pintype "passive"))
      (node (ref "C91") (pin "1") (pinfunction "1_1") (pintype "passive"))
      (node (ref "C92") (pin "1") (pinfunction "1_1") (pintype "passive"))
      (node (ref "C93") (pin "1") (pinfunction "1_1") (pintype "passive"))
      (node (ref "C94") (pin "1") (pinfunction "1_1") (pintype "passive"))
      (node (ref "C95") (pin "1") (pinfunction "1_1") (pintype "passive"))
      (node (ref "C96") (pin "1") (pinfunction "1_1") (pintype "passive"))
      (node (ref "FB2") (pin "2") (pinfunction "2_2") (pintype "passive"))
      (node (ref "R77") (pin "1") (pinfunction "1_1") (pintype "passive"))
      (node (ref "U1") (pin "H14") (pinfunction "VDDARM_IN_1_H14") (pintype "power_in"))
      (node (ref "U1") (pin "J14") (pinfunction "VDDARM_IN_2_J14") (pintype "power_in"))
      (node (ref "U1") (pin "K14") (pinfunction "VDDARM_IN_3_K14") (pintype "power_in"))
      (node (ref "U1") (pin "K9") (pinfunction "VDDARM23_IN_1_K9") (pintype "power_in"))
      (node (ref "U1") (pin "L14") (pinfunction "VDDARM_IN_4_L14") (pintype "power_in"))
      (node (ref "U1") (pin "L9") (pinfunction "VDDARM23_IN_2_L9") (pintype "power_in"))
      (node (ref "U1") (pin "M14") (pinfunction "VDDARM_IN_5_M14") (pintype "power_in"))
      (node (ref "U1") (pin "M9") (pinfunction "VDDARM23_IN_3_M9") (pintype "power_in"))
      (node (ref "U1") (pin "N14") (pinfunction "VDDARM_IN_6_N14") (pintype "power_in"))
      (node (ref "U1") (pin "N9") (pinfunction "VDDARM23_IN_4_N9") (pintype "power_in"))
      (node (ref "U1") (pin "P14") (pinfunction "VDDARM_IN_7_P14") (pintype "power_in"))
      (node (ref "U1") (pin "P9") (pinfunction "VDDARM23_IN_5_P9") (pintype "power_in"))
      (node (ref "U1") (pin "R14") (pinfunction "VDDARM_IN_8_R14") (pintype "power_in"))
      (node (ref "U1") (pin "R9") (pinfunction "VDDARM23_IN_6_R9") (pintype "power_in"))
      (node (ref "U1") (pin "T9") (pinfunction "VDDARM23_IN_7_T9") (pintype "power_in"))
      (node (ref "U1") (pin "U9") (pinfunction "VDDARM23_IN_8_U9") (pintype "power_in"))
    )
    (net (code "5") (name "+2V5") (class "Default")
      (node (ref "C153") (pin "1") (pinfunction "1_1") (pintype "passive"))
      (node (ref "R74") (pin "2") (pinfunction "2_2") (pintype "passive"))
      (node (ref "R78") (pin "2") (pinfunction "2_2") (pintype "passive"))
      (node (ref "R80") (pin "2") (pinfunction "2_2") (pintype "passive"))
    )
    (net (code "6") (name "+3V0_ALWAYS") (class "Default")
      (node (ref "C136") (pin "1") (pinfunction "1_1") (pintype "passive"))
      (node (ref "C137") (pin "1") (pinfunction "1_1") (pintype "passive"))
      (node (ref "C142") (pin "1") (pinfunction "1_1") (pintype "passive"))
      (node (ref "U1") (pin "G11") (pinfunction "VDD_SNVS_IN_G11") (pintype "power_in"))
      (node (ref "U1") (pin "H9") (pinfunction "VDDHIGH_IN_1_H9") (pintype "power_in"))
      (node (ref "U1") (pin "J9") (pinfunction "VDDHIGH_IN_2_J9") (pintype "power_in"))
    )
    (net (code "7") (name "+3V3") (class "Default")
      (node (ref "C144") (pin "1") (pinfunction "1_1") (pintype "passive"))
      (node (ref "C146") (pin "1") (pinfunction "1_1") (pintype "passive"))
      (node (ref "C147") (pin "1") (pinfunction "1_1") (pintype "passive"))
      (node (ref "C148") (pin "1") (pinfunction "1_1") (pintype "passive"))
      (node (ref "C154") (pin "1") (pinfunction "1_1") (pintype "passive"))
      (node (ref "C163") (pin "1") (pinfunction "1_1") (pintype "passive"))
      (node (ref "C164") (pin "1") (pinfunction "1_1") (pintype "passive"))
      (node (ref "C165") (pin "1") (pinfunction "1_1") (pintype "passive"))
      (node (ref "C166") (pin "1") (pinfunction "1_1") (pintype "passive"))
      (node (ref "C174") (pin "1") (pinfunction "1_1") (pintype "passive"))
      (node (ref "R76") (pin "2") (pinfunction "2_2") (pintype "passive"))
      (node (ref "U1") (pin "G14") (pinfunction "NVCC_SD3_G14") (pintype "power_in"))
      (node (ref "U1") (pin "G15") (pinfunction "NVCC_NANDF_G15") (pintype "power_in"))
      (node (ref "U1") (pin "G16") (pinfunction "NVCC_SD1_G16") (pintype "power_in"))
      (node (ref "U1") (pin "G17") (pinfunction "NVCC_SD2_G17") (pintype "power_in"))
      (node (ref "U1") (pin "J7") (pinfunction "NVCC_JTAG_J7") (pintype "power_in"))
      (node (ref "U1") (pin "K19") (pinfunction "NVCC_EIM0_K19") (pintype "power_in"))
      (node (ref "U1") (pin "L19") (pinfunction "NVCC_EIM1_L19") (pintype "power_in"))
      (node (ref "U1") (pin "M19") (pinfunction "NVCC_EIM2_M19") (pintype "power_in"))
      (node (ref "U1") (pin "P19") (pinfunction "NVCC_LCD_P19") (pintype "power_in"))
      (node (ref "U1") (pin "P7") (pinfunction "NVCC_GPIO_P7") (pintype "power_in"))
    )
    (net (code "8") (name "/+1V1_NVCC_PLL_OUT") (class "Default")
      (node (ref "C150") (pin "1") (pinfunction "1_1") (pintype "passive"))
      (node (ref "C151") (pin "1") (pinfunction "1_1") (pintype "passive"))
      (node (ref "R105") (pin "1") (pinfunction "1_1") (pintype "passive"))
      (node (ref "R77") (pin "2") (pinfunction "2_2") (pintype "passive"))
      (node (ref "R79") (pin "2") (pinfunction "2_2") (pintype "passive"))
      (node (ref "U1") (pin "E8") (pinfunction "NVCC_PLL_OUT_E8") (pintype "power_in"))
    )
    (net (code "9") (name "/+1V2_VDD_ARM_CAP") (class "Default")
      (node (ref "C100") (pin "1") (pinfunction "1_1") (pintype "passive"))
      (node (ref "C101") (pin "1") (pinfunction "1_1") (pintype "passive"))
      (node (ref "C102") (pin "1") (pinfunction "1_1") (pintype "passive"))
      (node (ref "C103") (pin "1") (pinfunction "1_1") (pintype "passive"))
      (node (ref "C104") (pin "1") (pinfunction "1_1") (pintype "passive"))
      (node (ref "C105") (pin "1") (pinfunction "1_1") (pintype "passive"))
      (node (ref "C106") (pin "1") (pinfunction "1_1") (pintype "passive"))
      (node (ref "C97") (pin "1") (pinfunction "1_1") (pintype "passive"))
      (node (ref "C98") (pin "1") (pinfunction "1_1") (pintype "passive"))
      (node (ref "C99") (pin "1") (pinfunction "1_1") (pintype "passive"))
      (node (ref "U1") (pin "H11") (pinfunction "VDDARM23_CAP_1_H11") (pintype "power_in"))
      (node (ref "U1") (pin "H13") (pinfunction "VDDARM_CAP_1_H13") (pintype "power_in"))
      (node (ref "U1") (pin "J11") (pinfunction "VDDARM23_CAP_2_J11") (pintype "power_in"))
      (node (ref "U1") (pin "J13") (pinfunction "VDDARM_CAP_2_J13") (pintype "power_in"))
      (node (ref "U1") (pin "K11") (pinfunction "VDDARM23_CAP_3_K11") (pintype "power_in"))
      (node (ref "U1") (pin "K13") (pinfunction "VDDARM_CAP_3_K13") (pintype "power_in"))
      (node (ref "U1") (pin "L11") (pinfunction "VDDARM23_CAP_4_L11") (pintype "power_in"))
      (node (ref "U1") (pin "L13") (pinfunction "VDDARM_CAP_4_L13") (pintype "power_in"))
      (node (ref "U1") (pin "M11") (pinfunction "VDDARM23_CAP_5_M11") (pintype "power_in"))
      (node (ref "U1") (pin "M13") (pinfunction "VDDARM_CAP_5_M13") (pintype "power_in"))
      (node (ref "U1") (pin "N11") (pinfunction "VDDARM23_CAP_6_N11") (pintype "power_in"))
      (node (ref "U1") (pin "N13") (pinfunction "VDDARM_CAP_6_N13") (pintype "power_in"))
      (node (ref "U1") (pin "P11") (pinfunction "VDDARM23_CAP_7_P11") (pintype "power_in"))
      (node (ref "U1") (pin "P13") (pinfunction "VDDARM_CAP_7_P13") (pintype "power_in"))
      (node (ref "U1") (pin "R11") (pinfunction "VDDARM23_CAP_8_R11") (pintype "power_in"))
      (node (ref "U1") (pin "R13") (pinfunction "VDDARM_CAP_8_R13") (pintype "power_in"))
    )
    (net (code "10") (name "/+1V375_VDDSOC_IN") (class "Default")
      (node (ref "C119") (pin "1") (pinfunction "1_1") (pintype "passive"))
      (node (ref "C120") (pin "1") (pinfunction "1_1") (pintype "passive"))
      (node (ref "C121") (pin "1") (pinfunction "1_1") (pintype "passive"))
      (node (ref "C122") (pin "1") (pinfunction "1_1") (pintype "passive"))
      (node (ref "C123") (pin "1") (pinfunction "1_1") (pintype "passive"))
      (node (ref "C124") (pin "1") (pinfunction "1_1") (pintype "passive"))
      (node (ref "C125") (pin "1") (pinfunction "1_1") (pintype "passive"))
      (node (ref "C126") (pin "1") (pinfunction "1_1") (pintype "passive"))
      (node (ref "C127") (pin "1") (pinfunction "1_1") (pintype "passive"))
      (node (ref "C128") (pin "1") (pinfunction "1_1") (pintype "passive"))
      (node (ref "C129") (pin "1") (pinfunction "1_1") (pintype "passive"))
      (node (ref "FB2") (pin "1") (pinfunction "1_1") (pintype "passive"))
      (node (ref "U1") (pin "H16") (pinfunction "VDDSOC_IN_1_H16") (pintype "power_in"))
      (node (ref "U1") (pin "J16") (pinfunction "VDDSOC_IN_2_J16") (pintype "power_in"))
      (node (ref "U1") (pin "K16") (pinfunction "VDDSOC_IN_3_K16") (pintype "power_in"))
      (node (ref "U1") (pin "L16") (pinfunction "VDDSOC_IN_4_L16") (pintype "power_in"))
      (node (ref "U1") (pin "M16") (pinfunction "VDDSOC_IN_5_M16") (pintype "power_in"))
      (node (ref "U1") (pin "N16") (pinfunction "VDDSOC_IN_6_N16") (pintype "power_in"))
      (node (ref "U1") (pin "P16") (pinfunction "VDDSOC_IN_7_P16") (pintype "power_in"))
      (node (ref "U1") (pin "R16") (pinfunction "VDDSOC_IN_8_R16") (pintype "power_in"))
      (node (ref "U1") (pin "T16") (pinfunction "VDDSOC_IN_9_T16") (pintype "power_in"))
      (node (ref "U1") (pin "U16") (pinfunction "VDDSOC_IN_10_U16") (pintype "power_in"))
    )
    (net (code "11") (name "/+2V5_VDDHIGH_VPH") (class "Default")
      (node (ref "C139") (pin "2") (pinfunction "2_2") (pintype "passive"))
      (node (ref "C140") (pin "1") (pinfunction "1_1") (pintype "passive"))
      (node (ref "C141") (pin "1") (pinfunction "1_1") (pintype "passive"))
      (node (ref "U1") (pin "H10") (pinfunction "VDDHIGH_CAP_1_H10") (pintype "power_in"))
      (node (ref "U1") (pin "J10") (pinfunction "VDDHIGH_CAP_2_J10") (pintype "power_in"))
    )
    (net (code "12") (name "/+NVCC_CSI") (class "Default")
      (node (ref "C145") (pin "1") (pinfunction "1_1") (pintype "passive"))
      (node (ref "R76") (pin "1") (pinfunction "1_1") (pintype "passive"))
      (node (ref "U1") (pin "N7") (pinfunction "NVCC_CSI_N7") (pintype "power_in"))
    )
    (net (code "13") (name "/+NVCC_ENET") (class "Default")
      (node (ref "C155") (pin "1") (pinfunction "1_1") (pintype "passive"))
      (node (ref "C156") (pin "1") (pinfunction "1_1") (pintype "passive"))
      (node (ref "R74") (pin "1") (pinfunction "1_1") (pintype "passive"))
      (node (ref "U1") (pin "R19") (pinfunction "NVCC_ENET_R19") (pintype "power_in"))
    )
    (net (code "14") (name "/+NVCC_MIPI") (class "Default")
      (node (ref "C149") (pin "1") (pinfunction "1_1") (pintype "passive"))
      (node (ref "R78") (pin "1") (pinfunction "1_1") (pintype "passive"))
      (node (ref "U1") (pin "K7") (pinfunction "NVCC_MIPI_K7") (pintype "power_in"))
    )
    (net (code "15") (name "/+NVCC_RGMII") (class "Default")
      (node (ref "C152") (pin "1") (pinfunction "1_1") (pintype "passive"))
      (node (ref "R80") (pin "1") (pinfunction "1_1") (pintype "passive"))
      (node (ref "U1") (pin "G18") (pinfunction "NVCC_RGMII_G18") (pintype "power_in"))
    )
    (net (code "16") (name "/+VDDPU") (class "Default")
      (node (ref "C130") (pin "1") (pinfunction "1_1") (pintype "passive"))
      (node (ref "C131") (pin "1") (pinfunction "1_1") (pintype "passive"))
      (node (ref "C132") (pin "1") (pinfunction "1_1") (pintype "passive"))
      (node (ref "C133") (pin "1") (pinfunction "1_1") (pintype "passive"))
      (node (ref "C134") (pin "1") (pinfunction "1_1") (pintype "passive"))
      (node (ref "C135") (pin "1") (pinfunction "1_1") (pintype "passive"))
      (node (ref "U1") (pin "H17") (pinfunction "VDDPU_CAP_1_H17") (pintype "power_in"))
      (node (ref "U1") (pin "J17") (pinfunction "VDDPU_CAP_2_J17") (pintype "power_in"))
      (node (ref "U1") (pin "K17") (pinfunction "VDDPU_CAP_3_K17") (pintype "power_in"))
      (node (ref "U1") (pin "L17") (pinfunction "VDDPU_CAP_4_L17") (pintype "power_in"))
      (node (ref "U1") (pin "M17") (pinfunction "VDDPU_CAP_5_M17") (pintype "power_in"))
      (node (ref "U1") (pin "N17") (pinfunction "VDDPU_CAP_6_N17") (pintype "power_in"))
      (node (ref "U1") (pin "P17") (pinfunction "VDDPU_CAP_7_P17") (pintype "power_in"))
    )
    (net (code "17") (name "/+VDD_SNVS_CAP") (class "Default")
      (node (ref "C143") (pin "1") (pinfunction "1_1") (pintype "passive"))
      (node (ref "U1") (pin "G9") (pinfunction "VDD_SNVS_CAP_G9") (pintype "power_in"))
    )
    (net (code "18") (name "GND") (class "Default")
      (node (ref "C100") (pin "2") (pinfunction "2_2") (pintype "passive"))
      (node (ref "C101") (pin "2") (pinfunction "2_2") (pintype "passive"))
      (node (ref "C102") (pin "2") (pinfunction "2_2") (pintype "passive"))
      (node (ref "C103") (pin "2") (pinfunction "2_2") (pintype "passive"))
      (node (ref "C104") (pin "2") (pinfunction "2_2") (pintype "passive"))
      (node (ref "C105") (pin "2") (pinfunction "2_2") (pintype "passive"))
      (node (ref "C106") (pin "2") (pinfunction "2_2") (pintype "passive"))
      (node (ref "C107") (pin "2") (pinfunction "2_2") (pintype "passive"))
      (node (ref "C108") (pin "2") (pinfunction "2_2") (pintype "passive"))
      (node (ref "C109") (pin "2") (pinfunction "2_2") (pintype "passive"))
      (node (ref "C110") (pin "2") (pinfunction "2_2") (pintype "passive"))
      (node (ref "C111") (pin "2") (pinfunction "2_2") (pintype "passive"))
      (node (ref "C112") (pin "2") (pinfunction "2_2") (pintype "passive"))
      (node (ref "C113") (pin "2") (pinfunction "2_2") (pintype "passive"))
      (node (ref "C114") (pin "2") (pinfunction "2_2") (pintype "passive"))
      (node (ref "C115") (pin "2") (pinfunction "2_2") (pintype "passive"))
      (node (ref "C116") (pin "2") (pinfunction "2_2") (pintype "passive"))
      (node (ref "C117") (pin "2") (pinfunction "2_2") (pintype "passive"))
      (node (ref "C118") (pin "2") (pinfunction "2_2") (pintype "passive"))
      (node (ref "C119") (pin "2") (pinfunction "2_2") (pintype "passive"))
      (node (ref "C120") (pin "2") (pinfunction "2_2") (pintype "passive"))
      (node (ref "C121") (pin "2") (pinfunction "2_2") (pintype "passive"))
      (node (ref "C122") (pin "2") (pinfunction "2_2") (pintype "passive"))
      (node (ref "C123") (pin "2") (pinfunction "2_2") (pintype "passive"))
      (node (ref "C124") (pin "2") (pinfunction "2_2") (pintype "passive"))
      (node (ref "C125") (pin "2") (pinfunction "2_2") (pintype "passive"))
      (node (ref "C126") (pin "2") (pinfunction "2_2") (pintype "passive"))
      (node (ref "C127") (pin "2") (pinfunction "2_2") (pintype "passive"))
      (node (ref "C128") (pin "2") (pinfunction "2_2") (pintype "passive"))
      (node (ref "C129") (pin "2") (pinfunction "2_2") (pintype "passive"))
      (node (ref "C130") (pin "2") (pinfunction "2_2") (pintype "passive"))
      (node (ref "C131") (pin "2") (pinfunction "2_2") (pintype "passive"))
      (node (ref "C132") (pin "2") (pinfunction "2_2") (pintype "passive"))
      (node (ref "C133") (pin "2") (pinfunction "2_2") (pintype "passive"))
      (node (ref "C134") (pin "2") (pinfunction "2_2") (pintype "passive"))
      (node (ref "C135") (pin "2") (pinfunction "2_2") (pintype "passive"))
      (node (ref "C136") (pin "2") (pinfunction "2_2") (pintype "passive"))
      (node (ref "C137") (pin "2") (pinfunction "2_2") (pintype "passive"))
      (node (ref "C138") (pin "2") (pinfunction "2_2") (pintype "passive"))
      (node (ref "C139") (pin "1") (pinfunction "1_1") (pintype "passive"))
      (node (ref "C140") (pin "2") (pinfunction "2_2") (pintype "passive"))
      (node (ref "C141") (pin "2") (pinfunction "2_2") (pintype "passive"))
      (node (ref "C142") (pin "2") (pinfunction "2_2") (pintype "passive"))
      (node (ref "C143") (pin "2") (pinfunction "2_2") (pintype "passive"))
      (node (ref "C144") (pin "2") (pinfunction "2_2") (pintype "passive"))
      (node (ref "C145") (pin "2") (pinfunction "2_2") (pintype "passive"))
      (node (ref "C146") (pin "2") (pinfunction "2_2") (pintype "passive"))
      (node (ref "C147") (pin "2") (pinfunction "2_2") (pintype "passive"))
      (node (ref "C148") (pin "2") (pinfunction "2_2") (pintype "passive"))
      (node (ref "C149") (pin "2") (pinfunction "2_2") (pintype "passive"))
      (node (ref "C150") (pin "2") (pinfunction "2_2") (pintype "passive"))
      (node (ref "C151") (pin "2") (pinfunction "2_2") (pintype "passive"))
      (node (ref "C152") (pin "2") (pinfunction "2_2") (pintype "passive"))
      (node (ref "C153") (pin "2") (pinfunction "2_2") (pintype "passive"))
      (node (ref "C154") (pin "2") (pinfunction "2_2") (pintype "passive"))
      (node (ref "C155") (pin "2") (pinfunction "2_2") (pintype "passive"))
      (node (ref "C156") (pin "2") (pinfunction "2_2") (pintype "passive"))
      (node (ref "C157") (pin "2") (pinfunction "2_2") (pintype "passive"))
      (node (ref "C158") (pin "2") (pinfunction "2_2") (pintype "passive"))
      (node (ref "C159") (pin "2") (pinfunction "2_2") (pintype "passive"))
      (node (ref "C160") (pin "2") (pinfunction "2_2") (pintype "passive"))
      (node (ref "C161") (pin "2") (pinfunction "2_2") (pintype "passive"))
      (node (ref "C162") (pin "2") (pinfunction "2_2") (pintype "passive"))
      (node (ref "C163") (pin "2") (pinfunction "2_2") (pintype "passive"))
      (node (ref "C164") (pin "2") (pinfunction "2_2") (pintype "passive"))
      (node (ref "C165") (pin "2") (pinfunction "2_2") (pintype "passive"))
      (node (ref "C166") (pin "2") (pinfunction "2_2") (pintype "passive"))
      (node (ref "C167") (pin "2") (pinfunction "2_2") (pintype "passive"))
      (node (ref "C168") (pin "2") (pinfunction "2_2") (pintype "passive"))
      (node (ref "C169") (pin "2") (pinfunction "2_2") (pintype "passive"))
      (node (ref "C170") (pin "2") (pinfunction "2_2") (pintype "passive"))
      (node (ref "C171") (pin "2") (pinfunction "2_2") (pintype "passive"))
      (node (ref "C172") (pin "2") (pinfunction "2_2") (pintype "passive"))
      (node (ref "C173") (pin "2") (pinfunction "2_2") (pintype "passive"))
      (node (ref "C174") (pin "2") (pinfunction "2_2") (pintype "passive"))
      (node (ref "C90") (pin "2") (pinfunction "2_2") (pintype "passive"))
      (node (ref "C91") (pin "2") (pinfunction "2_2") (pintype "passive"))
      (node (ref "C92") (pin "2") (pinfunction "2_2") (pintype "passive"))
      (node (ref "C93") (pin "2") (pinfunction "2_2") (pintype "passive"))
      (node (ref "C94") (pin "2") (pinfunction "2_2") (pintype "passive"))
      (node (ref "C95") (pin "2") (pinfunction "2_2") (pintype "passive"))
      (node (ref "C96") (pin "2") (pinfunction "2_2") (pintype "passive"))
      (node (ref "C97") (pin "2") (pinfunction "2_2") (pintype "passive"))
      (node (ref "C98") (pin "2") (pinfunction "2_2") (pintype "passive"))
      (node (ref "C99") (pin "2") (pinfunction "2_2") (pintype "passive"))
      (node (ref "R79") (pin "1") (pinfunction "1_1") (pintype "passive"))
      (node (ref "U1") (pin "A13") (pinfunction "GND_1_A13") (pintype "power_in"))
      (node (ref "U1") (pin "A25") (pinfunction "GND_2_A25") (pintype "power_in"))
      (node (ref "U1") (pin "A4") (pinfunction "GND_3_A4") (pintype "power_in"))
      (node (ref "U1") (pin "A5") (pinfunction "FA_ANA_A5") (pintype "power_in"))
      (node (ref "U1") (pin "A8") (pinfunction "GND_4_A8") (pintype "power_in"))
      (node (ref "U1") (pin "AA10") (pinfunction "GND_5_AA10") (pintype "power_in"))
      (node (ref "U1") (pin "AA13") (pinfunction "GND_6_AA13") (pintype "power_in"))
      (node (ref "U1") (pin "AA16") (pinfunction "GND_7_AA16") (pintype "power_in"))
      (node (ref "U1") (pin "AA19") (pinfunction "GND_8_AA19") (pintype "power_in"))
      (node (ref "U1") (pin "AA22") (pinfunction "GND_9_AA22") (pintype "power_in"))
      (node (ref "U1") (pin "AA7") (pinfunction "GND_10_AA7") (pintype "power_in"))
      (node (ref "U1") (pin "AB24") (pinfunction "GND_11_AB24") (pintype "power_in"))
      (node (ref "U1") (pin "AB3") (pinfunction "GND_12_AB3") (pintype "power_in"))
      (node (ref "U1") (pin "AD10") (pinfunction "GND_13_AD10") (pintype "power_in"))
      (node (ref "U1") (pin "AD13") (pinfunction "GND_14_AD13") (pintype "power_in"))
      (node (ref "U1") (pin "AD16") (pinfunction "GND_15_AD16") (pintype "power_in"))
      (node (ref "U1") (pin "AD19") (pinfunction "GND_16_AD19") (pintype "power_in"))
      (node (ref "U1") (pin "AD22") (pinfunction "GND_17_AD22") (pintype "power_in"))
      (node (ref "U1") (pin "AD4") (pinfunction "GND_18_AD4") (pintype "power_in"))
      (node (ref "U1") (pin "AD7") (pinfunction "GND_19_AD7") (pintype "power_in"))
      (node (ref "U1") (pin "AE1") (pinfunction "GND_20_AE1") (pintype "power_in"))
      (node (ref "U1") (pin "AE25") (pinfunction "GND_21_AE25") (pintype "power_in"))
      (node (ref "U1") (pin "B4") (pinfunction "GND_22_B4") (pintype "power_in"))
      (node (ref "U1") (pin "B5") (pinfunction "VDD_FA_B5") (pintype "power_in"))
      (node (ref "U1") (pin "C1") (pinfunction "GND_23_C1") (pintype "power_in"))
      (node (ref "U1") (pin "C10") (pinfunction "GND_24_C10") (pintype "power_in"))
      (node (ref "U1") (pin "C4") (pinfunction "GND_25_C4") (pintype "power_in"))
      (node (ref "U1") (pin "C6") (pinfunction "GND_26_C6") (pintype "power_in"))
      (node (ref "U1") (pin "D3") (pinfunction "GND_27_D3") (pintype "power_in"))
      (node (ref "U1") (pin "D6") (pinfunction "GND_28_D6") (pintype "power_in"))
      (node (ref "U1") (pin "D8") (pinfunction "GND_29_D8") (pintype "power_in"))
      (node (ref "U1") (pin "E5") (pinfunction "GND_30_E5") (pintype "power_in"))
      (node (ref "U1") (pin "E6") (pinfunction "GND_31_E6") (pintype "power_in"))
      (node (ref "U1") (pin "E7") (pinfunction "GND_32_E7") (pintype "power_in"))
      (node (ref "U1") (pin "F5") (pinfunction "GND_33_F5") (pintype "power_in"))
      (node (ref "U1") (pin "F6") (pinfunction "GND_34_F6") (pintype "power_in"))
      (node (ref "U1") (pin "F7") (pinfunction "GND_35_F7") (pintype "power_in"))
      (node (ref "U1") (pin "F8") (pinfunction "GND_36_F8") (pintype "power_in"))
      (node (ref "U1") (pin "G10") (pinfunction "GND_37_G10") (pintype "power_in"))
      (node (ref "U1") (pin "G19") (pinfunction "GND_38_G19") (pintype "power_in"))
      (node (ref "U1") (pin "G3") (pinfunction "GND_39_G3") (pintype "power_in"))
      (node (ref "U1") (pin "H12") (pinfunction "GND_40_H12") (pintype "power_in"))
      (node (ref "U1") (pin "H15") (pinfunction "GND_41_H15") (pintype "power_in"))
      (node (ref "U1") (pin "H18") (pinfunction "GND_42_H18") (pintype "power_in"))
      (node (ref "U1") (pin "H8") (pinfunction "GND_43_H8") (pintype "power_in"))
      (node (ref "U1") (pin "J12") (pinfunction "GND_44_J12") (pintype "power_in"))
      (node (ref "U1") (pin "J15") (pinfunction "GND_45_J15") (pintype "power_in"))
      (node (ref "U1") (pin "J18") (pinfunction "GND_46_J18") (pintype "power_in"))
      (node (ref "U1") (pin "J2") (pinfunction "GND_47_J2") (pintype "power_in"))
      (node (ref "U1") (pin "J8") (pinfunction "GND_48_J8") (pintype "power_in"))
      (node (ref "U1") (pin "K10") (pinfunction "GND_49_K10") (pintype "power_in"))
      (node (ref "U1") (pin "K12") (pinfunction "GND_50_K12") (pintype "power_in"))
      (node (ref "U1") (pin "K15") (pinfunction "GND_51_K15") (pintype "power_in"))
      (node (ref "U1") (pin "K18") (pinfunction "GND_52_K18") (pintype "power_in"))
      (node (ref "U1") (pin "K8") (pinfunction "GND_53_K8") (pintype "power_in"))
      (node (ref "U1") (pin "L10") (pinfunction "GND_54_L10") (pintype "power_in"))
      (node (ref "U1") (pin "L12") (pinfunction "GND_55_L12") (pintype "power_in"))
      (node (ref "U1") (pin "L15") (pinfunction "GND_56_L15") (pintype "power_in"))
      (node (ref "U1") (pin "L18") (pinfunction "GND_57_L18") (pintype "power_in"))
      (node (ref "U1") (pin "L2") (pinfunction "GND_58_L2") (pintype "power_in"))
      (node (ref "U1") (pin "L5") (pinfunction "GND_59_L5") (pintype "power_in"))
      (node (ref "U1") (pin "L8") (pinfunction "GND_60_L8") (pintype "power_in"))
      (node (ref "U1") (pin "M10") (pinfunction "GND_61_M10") (pintype "power_in"))
      (node (ref "U1") (pin "M12") (pinfunction "GND_62_M12") (pintype "power_in"))
      (node (ref "U1") (pin "M15") (pinfunction "GND_63_M15") (pintype "power_in"))
      (node (ref "U1") (pin "M18") (pinfunction "GND_64_M18") (pintype "power_in"))
      (node (ref "U1") (pin "M8") (pinfunction "GND_65_M8") (pintype "power_in"))
      (node (ref "U1") (pin "N10") (pinfunction "GND_66_N10") (pintype "power_in"))
      (node (ref "U1") (pin "N15") (pinfunction "GND_67_N15") (pintype "power_in"))
      (node (ref "U1") (pin "N18") (pinfunction "GND_68_N18") (pintype "power_in"))
      (node (ref "U1") (pin "N8") (pinfunction "GND_69_N8") (pintype "power_in"))
      (node (ref "U1") (pin "P10") (pinfunction "GND_70_P10") (pintype "power_in"))
      (node (ref "U1") (pin "P12") (pinfunction "GND_71_P12") (pintype "power_in"))
      (node (ref "U1") (pin "P15") (pinfunction "GND_72_P15") (pintype "power_in"))
      (node (ref "U1") (pin "P18") (pinfunction "GND_73_P18") (pintype "power_in"))
      (node (ref "U1") (pin "P8") (pinfunction "GND_74_P8") (pintype "power_in"))
      (node (ref "U1") (pin "R12") (pinfunction "GND_75_R12") (pintype "power_in"))
      (node (ref "U1") (pin "R15") (pinfunction "GND_76_R15") (pintype "power_in"))
      (node (ref "U1") (pin "R17") (pinfunction "GND_77_R17") (pintype "power_in"))
      (node (ref "U1") (pin "R8") (pinfunction "GND_78_R8") (pintype "power_in"))
      (node (ref "U1") (pin "T11") (pinfunction "GND_79_T11") (pintype "power_in"))
      (node (ref "U1") (pin "T12") (pinfunction "GND_80_T12") (pintype "power_in"))
      (node (ref "U1") (pin "T15") (pinfunction "GND_81_T15") (pintype "power_in"))
      (node (ref "U1") (pin "T17") (pinfunction "GND_82_T17") (pintype "power_in"))
      (node (ref "U1") (pin "T19") (pinfunction "GND_83_T19") (pintype "power_in"))
      (node (ref "U1") (pin "T8") (pinfunction "GND_84_T8") (pintype "power_in"))
      (node (ref "U1") (pin "U11") (pinfunction "GND_85_U11") (pintype "power_in"))
      (node (ref "U1") (pin "U12") (pinfunction "GND_86_U12") (pintype "power_in"))
      (node (ref "U1") (pin "U15") (pinfunction "GND_87_U15") (pintype "power_in"))
      (node (ref "U1") (pin "U17") (pinfunction "GND_88_U17") (pintype "power_in"))
      (node (ref "U1") (pin "U19") (pinfunction "GND_90_U19") (pintype "power_in"))
      (node (ref "U1") (pin "U8") (pinfunction "GND_89_U8") (pintype "power_in"))
      (node (ref "U1") (pin "V19") (pinfunction "GND_92_V19") (pintype "power_in"))
      (node (ref "U1") (pin "V8") (pinfunction "GND_91_V8") (pintype "power_in"))
      (node (ref "U1") (pin "W10") (pinfunction "GND_97_W10") (pintype "power_in"))
      (node (ref "U1") (pin "W11") (pinfunction "GND_98_W11") (pintype "power_in"))
      (node (ref "U1") (pin "W12") (pinfunction "GND_99_W12") (pintype "power_in"))
      (node (ref "U1") (pin "W13") (pinfunction "GND_100_W13") (pintype "power_in"))
      (node (ref "U1") (pin "W15") (pinfunction "GND_101_W15") (pintype "power_in"))
      (node (ref "U1") (pin "W16") (pinfunction "GND_102_W16") (pintype "power_in"))
      (node (ref "U1") (pin "W17") (pinfunction "GND_103_W17") (pintype "power_in"))
      (node (ref "U1") (pin "W18") (pinfunction "GND_104_W18") (pintype "power_in"))
      (node (ref "U1") (pin "W19") (pinfunction "GND_105_W19") (pintype "power_in"))
      (node (ref "U1") (pin "W3") (pinfunction "GND_93_W3") (pintype "power_in"))
      (node (ref "U1") (pin "W7") (pinfunction "GND_94_W7") (pintype "power_in"))
      (node (ref "U1") (pin "W8") (pinfunction "GND_95_W8") (pintype "power_in"))
      (node (ref "U1") (pin "W9") (pinfunction "GND_96_W9") (pintype "power_in"))
      (node (ref "U1") (pin "Y24") (pinfunction "GND_107_Y24") (pintype "power_in"))
      (node (ref "U1") (pin "Y5") (pinfunction "GND_106_Y5") (pintype "power_in"))
    )
    (net (code "19") (name "unconnected-(U1B-GPANAIO-PadC8)") (class "Default")
      (node (ref "U1") (pin "C8") (pinfunction "GPANAIO_C8") (pintype "power_in+no_connect"))
    )
  )
)
